# Lab5Prep.net
KiCad netlist of a schematic drawn in EAGLE
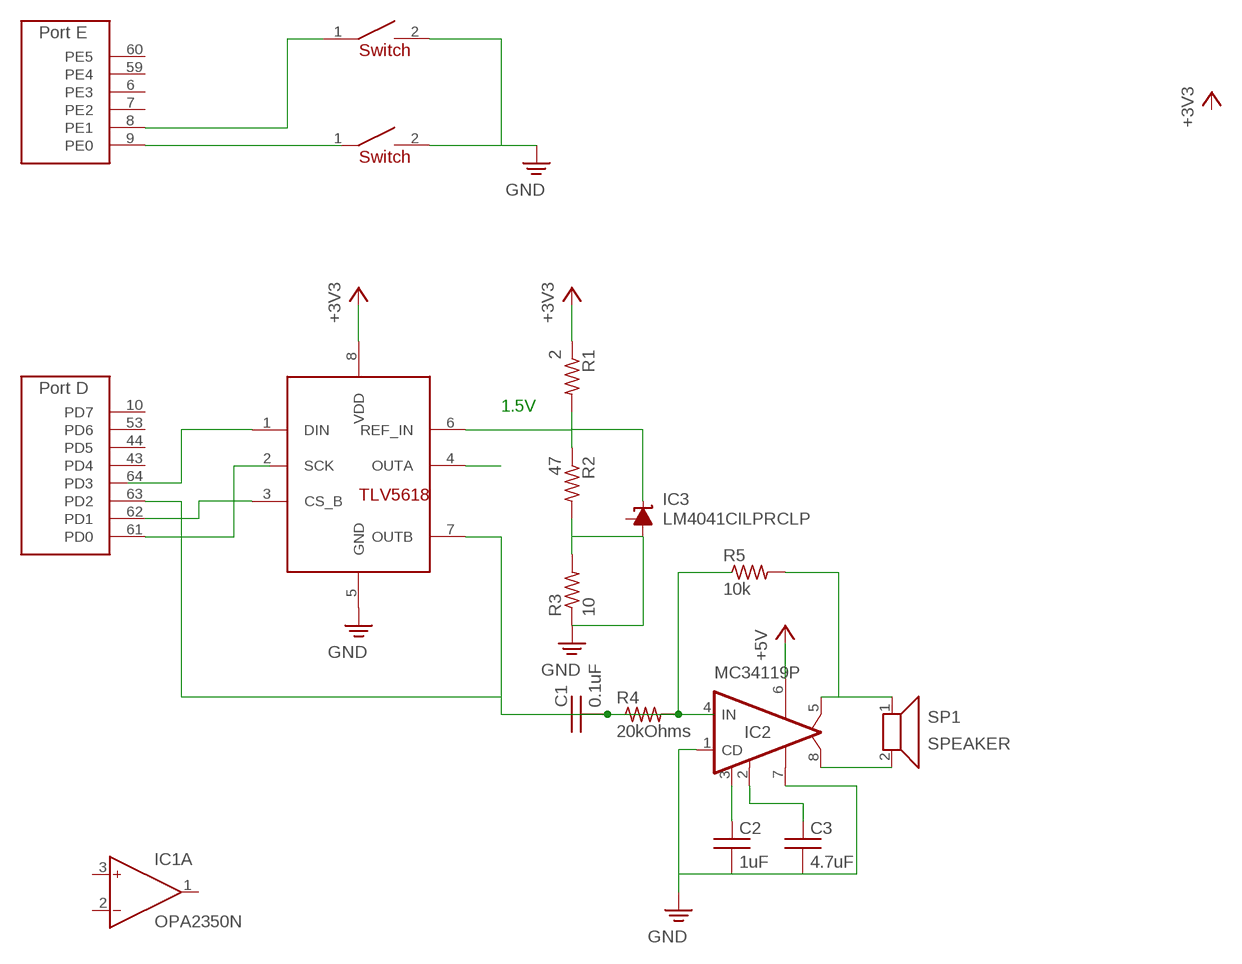
[diagram p0: schematic, sheet 1]

(export (version "E")
  (design (tool "Eeschema 10.0.6"))
  (components
    (comp (ref "C1")
      (value "0.1uF")
      (footprint "eagle-import:CAP100MIL")
      (libsource (lib "eagle-import") (part "CAPACITOR025-024X044"))
    )
    (comp (ref "C2")
      (value "1uF")
      (footprint "eagle-import:CAP100MIL")
      (libsource (lib "eagle-import") (part "CAPACITOR025-024X044"))
    )
    (comp (ref "C3")
      (value "4.7uF")
      (footprint "eagle-import:CAP100MIL")
      (libsource (lib "eagle-import") (part "CAPACITOR025-024X044"))
    )
    (comp (ref "IC1")
      (value "OPA2350N")
      (footprint "eagle-import:DIL08")
      (libsource (lib "eagle-import") (part "OPA2350N"))
    )
    (comp (ref "IC2")
      (value "MC34119P")
      (footprint "eagle-import:DIL08")
      (libsource (lib "eagle-import") (part "MC34119P"))
    )
    (comp (ref "IC3")
      (value "LM4041CILPRCLP")
      (footprint "eagle-import:LP_O-PBCY-W3")
      (fields (field (name "MPN") "LM4041CILP"))
      (libsource (lib "eagle-import") (part "LM4041CILPRLPC"))
    )
    (comp (ref "R1")
      (value "2")
      (footprint "eagle-import:RES300MIL")
      (libsource (lib "eagle-import") (part "RESISTOR0204/7"))
    )
    (comp (ref "R2")
      (value "47")
      (footprint "eagle-import:RES300MIL")
      (libsource (lib "eagle-import") (part "RESISTOR0204/7"))
    )
    (comp (ref "R3")
      (value "10")
      (footprint "eagle-import:RES300MIL")
      (libsource (lib "eagle-import") (part "RESISTOR0204/7"))
    )
    (comp (ref "R4")
      (value "20kOhms")
      (footprint "eagle-import:RES200MIL")
      (libsource (lib "eagle-import") (part "RESISTOR0204/5"))
    )
    (comp (ref "R5")
      (value "10k")
      (footprint "eagle-import:RES200MIL")
      (libsource (lib "eagle-import") (part "RESISTOR0204/5"))
    )
    (comp (ref "SP1")
      (value "SPEAKER")
      (footprint "eagle-import:1X02")
      (libsource (lib "eagle-import") (part "SPEAKER"))
    )
    (comp (ref "U$1")
      (value "TM4C123GH6PM")
      (footprint "eagle-import:QFP50P1200X1200X160-64N")
      (libsource (lib "eagle-import") (part "TM4C123GH6PM"))
    )
    (comp (ref "U$2")
      (value "TLV5618")
      (footprint "eagle-import:DIL08")
      (libsource (lib "eagle-import") (part "TLV5618"))
    )
    (comp (ref "U$4")
      (value "SW_POWER_100MIL")
      (footprint "eagle-import:SW_POWER")
      (libsource (lib "eagle-import") (part "SW_POWER_100MIL"))
    )
    (comp (ref "U$5")
      (value "SW_POWER_100MIL")
      (footprint "eagle-import:SW_POWER")
      (libsource (lib "eagle-import") (part "SW_POWER_100MIL"))
    )
  )
  (nets
    (net (code "1") (name "+3V3") (class "Default")
      (node (ref "R1") (pin "1") (pinfunction "1_1") (pintype "passive"))
      (node (ref "U$2") (pin "8") (pinfunction "VDD_8") (pintype "bidirectional"))
    )
    (net (code "2") (name "+5V") (class "Default")
      (node (ref "IC2") (pin "6") (pinfunction "VCC_6") (pintype "power_in"))
    )
    (net (code "3") (name "GND") (class "Default")
      (node (ref "C2") (pin "2") (pinfunction "2_2") (pintype "passive"))
      (node (ref "C3") (pin "2") (pinfunction "2_2") (pintype "passive"))
      (node (ref "IC2") (pin "1") (pinfunction "CD_1") (pintype "passive"))
      (node (ref "IC2") (pin "7") (pinfunction "GND_7") (pintype "power_in"))
      (node (ref "IC3") (pin "3") (pinfunction "A_3") (pintype "passive"))
      (node (ref "R2") (pin "2") (pinfunction "2_2") (pintype "passive"))
      (node (ref "R3") (pin "1") (pinfunction "1_1") (pintype "passive"))
      (node (ref "R3") (pin "2") (pinfunction "2_2") (pintype "passive"))
      (node (ref "U$2") (pin "5") (pinfunction "GND_5") (pintype "bidirectional"))
      (node (ref "U$4") (pin "2") (pinfunction "P$2_2") (pintype "bidirectional"))
      (node (ref "U$5") (pin "2") (pinfunction "P$2_2") (pintype "bidirectional"))
    )
    (net (code "4") (name "Net-(IC2-FC1)") (class "Default")
      (node (ref "C2") (pin "1") (pinfunction "1_1") (pintype "passive"))
      (node (ref "IC2") (pin "3") (pinfunction "FC1_3") (pintype "passive"))
    )
    (net (code "5") (name "Net-(IC2-FC2)") (class "Default")
      (node (ref "C3") (pin "1") (pinfunction "1_1") (pintype "passive"))
      (node (ref "IC2") (pin "2") (pinfunction "FC2_2") (pintype "passive"))
    )
    (net (code "6") (name "Net-(IC2-VO1)") (class "Default")
      (node (ref "IC2") (pin "5") (pinfunction "VO1_5") (pintype "output"))
      (node (ref "R5") (pin "2") (pinfunction "2_2") (pintype "passive"))
      (node (ref "SP1") (pin "1") (pinfunction "1_1") (pintype "passive"))
    )
    (net (code "7") (name "Net-(IC2-VO2)") (class "Default")
      (node (ref "IC2") (pin "8") (pinfunction "VO2_8") (pintype "output"))
      (node (ref "SP1") (pin "2") (pinfunction "2_2") (pintype "passive"))
    )
    (net (code "8") (name "Net-(IC3-C)") (class "Default")
      (node (ref "IC3") (pin "2") (pinfunction "C_2") (pintype "passive"))
      (node (ref "R1") (pin "2") (pinfunction "2_2") (pintype "passive"))
      (node (ref "R2") (pin "1") (pinfunction "1_1") (pintype "passive"))
      (node (ref "U$2") (pin "6") (pinfunction "REF_IN_6") (pintype "bidirectional"))
    )
    (net (code "9") (name "Net-(U$1D-PD1)") (class "Default")
      (node (ref "U$1") (pin "62") (pinfunction "PD1_62") (pintype "bidirectional"))
      (node (ref "U$2") (pin "3") (pinfunction "CS_B_3") (pintype "bidirectional"))
    )
    (net (code "10") (name "Net-(U$1D-PD2)") (class "Default")
      (node (ref "C1") (pin "1") (pinfunction "1_1") (pintype "passive"))
      (node (ref "C1") (pin "2") (pinfunction "2_2") (pintype "passive"))
      (node (ref "R4") (pin "1") (pinfunction "1_1") (pintype "passive"))
      (node (ref "R4") (pin "2") (pinfunction "2_2") (pintype "passive"))
      (node (ref "U$1") (pin "63") (pinfunction "PD2_63") (pintype "bidirectional"))
      (node (ref "U$2") (pin "7") (pinfunction "OUTB_7") (pintype "bidirectional"))
    )
    (net (code "11") (name "Net-(U$1E-PE1)") (class "Default")
      (node (ref "U$1") (pin "8") (pinfunction "PE1_8") (pintype "bidirectional"))
      (node (ref "U$4") (pin "1") (pinfunction "P$1_1") (pintype "bidirectional"))
    )
    (net (code "12") (name "unconnected-(IC1A-IN+-Pad3)") (class "Default")
      (node (ref "IC1") (pin "3") (pinfunction "IN+_3") (pintype "input"))
    )
    (net (code "13") (name "unconnected-(IC1A-IN--Pad2)") (class "Default")
      (node (ref "IC1") (pin "2") (pinfunction "IN-_2") (pintype "input"))
    )
    (net (code "14") (name "unconnected-(IC1A-OUT-Pad1)") (class "Default")
      (node (ref "IC1") (pin "1") (pinfunction "OUT_1") (pintype "output"))
    )
    (net (code "15") (name "unconnected-(IC2-IN-Pad4)") (class "Default")
      (node (ref "IC2") (pin "4") (pinfunction "IN_4") (pintype "input"))
    )
    (net (code "16") (name "unconnected-(IC3-FB-Pad1)") (class "Default")
      (node (ref "IC3") (pin "1") (pinfunction "FB_1") (pintype "passive"))
    )
    (net (code "17") (name "unconnected-(R5-Pad1)") (class "Default")
      (node (ref "R5") (pin "1") (pinfunction "1_1") (pintype "passive"))
    )
    (net (code "18") (name "unconnected-(U$1D-PD0-Pad61)") (class "Default")
      (node (ref "U$1") (pin "61") (pinfunction "PD0_61") (pintype "bidirectional"))
    )
    (net (code "19") (name "unconnected-(U$1D-PD3-Pad64)") (class "Default")
      (node (ref "U$1") (pin "64") (pinfunction "PD3_64") (pintype "bidirectional"))
    )
    (net (code "20") (name "unconnected-(U$1D-PD4-Pad43)") (class "Default")
      (node (ref "U$1") (pin "43") (pinfunction "PD4_43") (pintype "bidirectional"))
    )
    (net (code "21") (name "unconnected-(U$1D-PD5-Pad44)") (class "Default")
      (node (ref "U$1") (pin "44") (pinfunction "PD5_44") (pintype "bidirectional"))
    )
    (net (code "22") (name "unconnected-(U$1D-PD6-Pad53)") (class "Default")
      (node (ref "U$1") (pin "53") (pinfunction "PD6_53") (pintype "bidirectional"))
    )
    (net (code "23") (name "unconnected-(U$1D-PD7-Pad10)") (class "Default")
      (node (ref "U$1") (pin "10") (pinfunction "PD7_10") (pintype "bidirectional"))
    )
    (net (code "24") (name "unconnected-(U$1E-PE0-Pad9)") (class "Default")
      (node (ref "U$1") (pin "9") (pinfunction "PE0_9") (pintype "bidirectional"))
    )
    (net (code "25") (name "unconnected-(U$1E-PE2-Pad7)") (class "Default")
      (node (ref "U$1") (pin "7") (pinfunction "PE2_7") (pintype "bidirectional"))
    )
    (net (code "26") (name "unconnected-(U$1E-PE3-Pad6)") (class "Default")
      (node (ref "U$1") (pin "6") (pinfunction "PE3_6") (pintype "bidirectional"))
    )
    (net (code "27") (name "unconnected-(U$1E-PE4-Pad59)") (class "Default")
      (node (ref "U$1") (pin "59") (pinfunction "PE4_59") (pintype "bidirectional"))
    )
    (net (code "28") (name "unconnected-(U$1E-PE5-Pad60)") (class "Default")
      (node (ref "U$1") (pin "60") (pinfunction "PE5_60") (pintype "bidirectional"))
    )
    (net (code "29") (name "unconnected-(U$2-DIN-Pad1)") (class "Default")
      (node (ref "U$2") (pin "1") (pinfunction "DIN_1") (pintype "bidirectional"))
    )
    (net (code "30") (name "unconnected-(U$2-OUTA-Pad4)") (class "Default")
      (node (ref "U$2") (pin "4") (pinfunction "OUTA_4") (pintype "bidirectional"))
    )
    (net (code "31") (name "unconnected-(U$2-SCK-Pad2)") (class "Default")
      (node (ref "U$2") (pin "2") (pinfunction "SCK_2") (pintype "bidirectional"))
    )
    (net (code "32") (name "unconnected-(U$5-P$1-Pad1)") (class "Default")
      (node (ref "U$5") (pin "1") (pinfunction "P$1_1") (pintype "bidirectional"))
    )
  )
)
